# Interfaces.net
KiCad netlist of a schematic drawn in Altium Designer
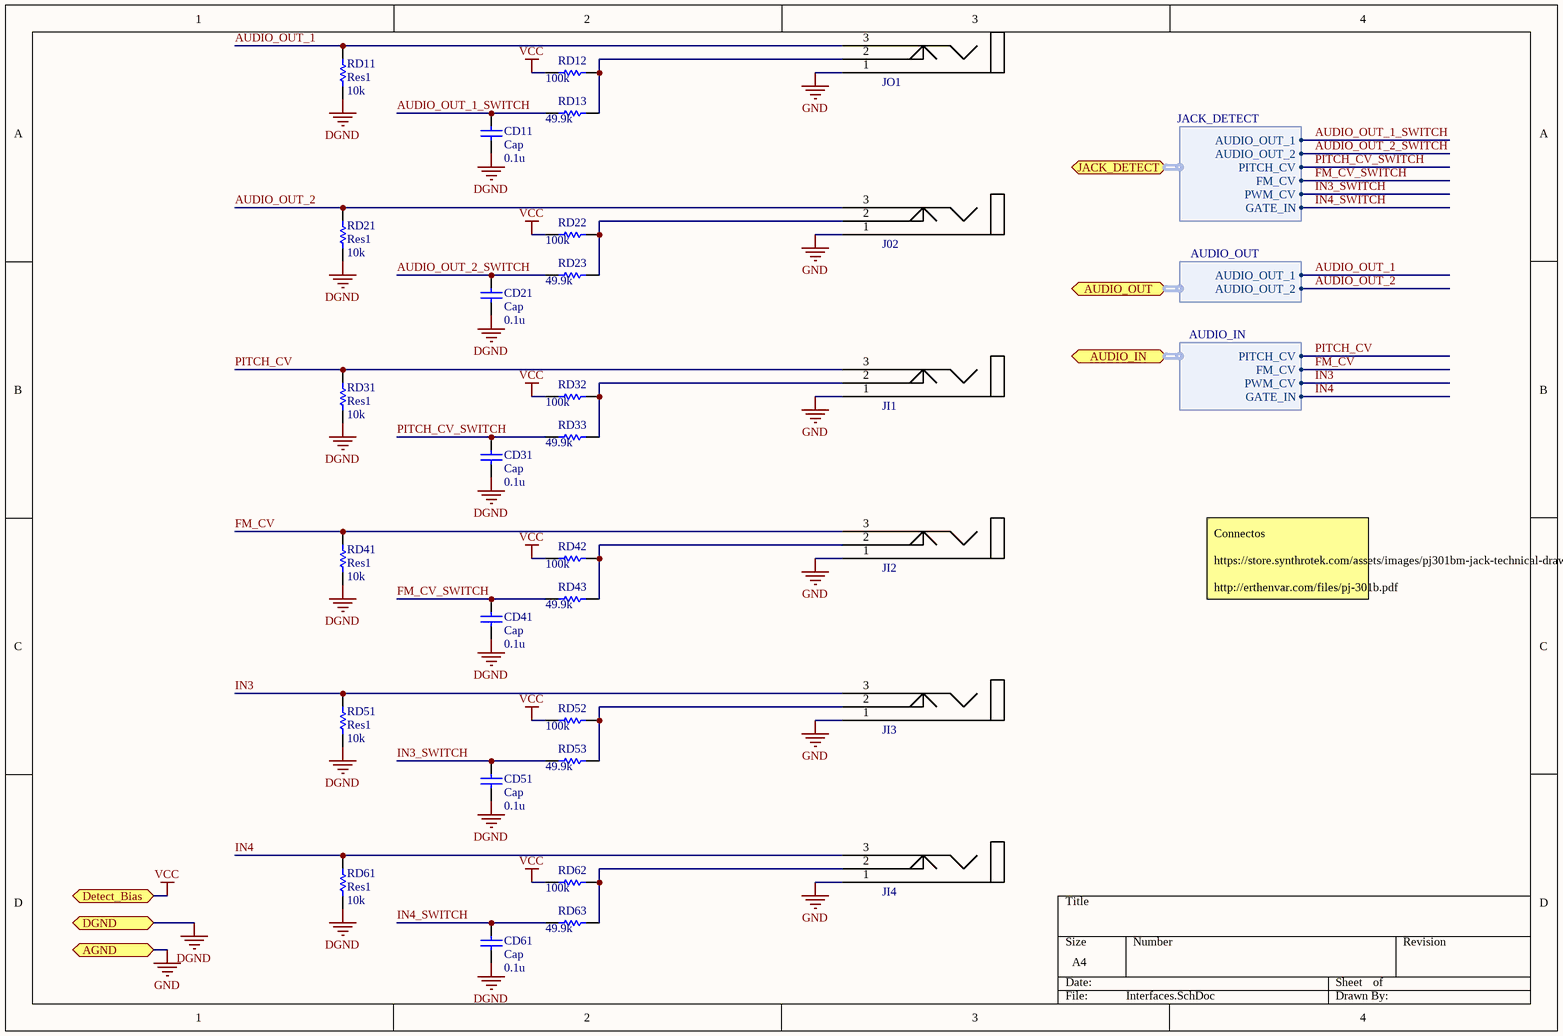
[diagram p0: Interfaces.SchDoc]

(export (version "E")
  (design (tool "Eeschema 10.0.6"))
  (components
    (comp (ref "CD11")
      (value "Cap")
      (footprint "C 0603 / 1608")
      (description "Capacitor")
      (fields (field (name "ALTIUM_VALUE") "0.1u") (field (name "PUBLISHER") "Altium Limited"))
      (libsource (lib "Standard") (part "Cap"))
    )
    (comp (ref "CD21")
      (value "Cap")
      (footprint "C 0603 / 1608")
      (description "Capacitor")
      (fields (field (name "ALTIUM_VALUE") "0.1u") (field (name "PUBLISHER") "Altium Limited"))
      (libsource (lib "Standard") (part "Cap"))
    )
    (comp (ref "CD31")
      (value "Cap")
      (footprint "C 0603 / 1608")
      (description "Capacitor")
      (fields (field (name "ALTIUM_VALUE") "0.1u") (field (name "PUBLISHER") "Altium Limited"))
      (libsource (lib "Standard") (part "Cap"))
    )
    (comp (ref "CD41")
      (value "Cap")
      (footprint "C 0603 / 1608")
      (description "Capacitor")
      (fields (field (name "ALTIUM_VALUE") "0.1u") (field (name "PUBLISHER") "Altium Limited"))
      (libsource (lib "Standard") (part "Cap"))
    )
    (comp (ref "CD51")
      (value "Cap")
      (footprint "C 0603 / 1608")
      (description "Capacitor")
      (fields (field (name "ALTIUM_VALUE") "0.1u") (field (name "PUBLISHER") "Altium Limited"))
      (libsource (lib "Standard") (part "Cap"))
    )
    (comp (ref "CD61")
      (value "Cap")
      (footprint "C 0603 / 1608")
      (description "Capacitor")
      (fields (field (name "ALTIUM_VALUE") "0.1u") (field (name "PUBLISHER") "Altium Limited"))
      (libsource (lib "Standard") (part "Cap"))
    )
    (comp (ref "J02") (value "PJ-301") (footprint "PJ-301BM") (libsource (lib "Connectors") (part "PJ-301")))
    (comp (ref "JI1") (value "PJ-301") (footprint "PJ-301BM") (libsource (lib "Connectors") (part "PJ-301")))
    (comp (ref "JI2") (value "PJ-301") (footprint "PJ-301BM") (libsource (lib "Connectors") (part "PJ-301")))
    (comp (ref "JI3") (value "PJ-301") (footprint "PJ-301BM") (libsource (lib "Connectors") (part "PJ-301")))
    (comp (ref "JI4") (value "PJ-301") (footprint "PJ-301BM") (libsource (lib "Connectors") (part "PJ-301")))
    (comp (ref "JO1") (value "PJ-301") (footprint "PJ-301BM") (libsource (lib "Connectors") (part "PJ-301")))
    (comp (ref "RD11")
      (value "Res1")
      (footprint "RES0603R")
      (description "Resistor")
      (fields (field (name "ALTIUM_VALUE") "10k") (field (name "PUBLISHER") "Altium Limited"))
      (libsource (lib "Standard") (part "Res1"))
    )
    (comp (ref "RD12")
      (value "100k")
      (footprint "RES0603R")
      (description "Resistor")
      (fields (field (name "Comment") "Res1") (field (name "PUBLISHER") "Altium Limited"))
      (libsource (lib "Standard") (part "Res1"))
    )
    (comp (ref "RD13")
      (value "49.9k")
      (footprint "RES0603R")
      (description "Resistor")
      (fields (field (name "Comment") "Res1") (field (name "PUBLISHER") "Altium Limited"))
      (libsource (lib "Standard") (part "Res1"))
    )
    (comp (ref "RD21")
      (value "Res1")
      (footprint "RES0603R")
      (description "Resistor")
      (fields (field (name "ALTIUM_VALUE") "10k") (field (name "PUBLISHER") "Altium Limited"))
      (libsource (lib "Standard") (part "Res1"))
    )
    (comp (ref "RD22")
      (value "100k")
      (footprint "RES0603R")
      (description "Resistor")
      (fields (field (name "Comment") "Res1") (field (name "PUBLISHER") "Altium Limited"))
      (libsource (lib "Standard") (part "Res1"))
    )
    (comp (ref "RD23")
      (value "49.9k")
      (footprint "RES0603R")
      (description "Resistor")
      (fields (field (name "Comment") "Res1") (field (name "PUBLISHER") "Altium Limited"))
      (libsource (lib "Standard") (part "Res1"))
    )
    (comp (ref "RD31")
      (value "Res1")
      (footprint "RES0603R")
      (description "Resistor")
      (fields (field (name "ALTIUM_VALUE") "10k") (field (name "PUBLISHER") "Altium Limited"))
      (libsource (lib "Standard") (part "Res1"))
    )
    (comp (ref "RD32")
      (value "100k")
      (footprint "RES0603R")
      (description "Resistor")
      (fields (field (name "Comment") "Res1") (field (name "PUBLISHER") "Altium Limited"))
      (libsource (lib "Standard") (part "Res1"))
    )
    (comp (ref "RD33")
      (value "49.9k")
      (footprint "RES0603R")
      (description "Resistor")
      (fields (field (name "Comment") "Res1") (field (name "PUBLISHER") "Altium Limited"))
      (libsource (lib "Standard") (part "Res1"))
    )
    (comp (ref "RD41")
      (value "Res1")
      (footprint "RES0603R")
      (description "Resistor")
      (fields (field (name "ALTIUM_VALUE") "10k") (field (name "PUBLISHER") "Altium Limited"))
      (libsource (lib "Standard") (part "Res1"))
    )
    (comp (ref "RD42")
      (value "100k")
      (footprint "RES0603R")
      (description "Resistor")
      (fields (field (name "Comment") "Res1") (field (name "PUBLISHER") "Altium Limited"))
      (libsource (lib "Standard") (part "Res1"))
    )
    (comp (ref "RD43")
      (value "49.9k")
      (footprint "RES0603R")
      (description "Resistor")
      (fields (field (name "Comment") "Res1") (field (name "PUBLISHER") "Altium Limited"))
      (libsource (lib "Standard") (part "Res1"))
    )
    (comp (ref "RD51")
      (value "Res1")
      (footprint "RES0603R")
      (description "Resistor")
      (fields (field (name "ALTIUM_VALUE") "10k") (field (name "PUBLISHER") "Altium Limited"))
      (libsource (lib "Standard") (part "Res1"))
    )
    (comp (ref "RD52")
      (value "100k")
      (footprint "RES0603R")
      (description "Resistor")
      (fields (field (name "Comment") "Res1") (field (name "PUBLISHER") "Altium Limited"))
      (libsource (lib "Standard") (part "Res1"))
    )
    (comp (ref "RD53")
      (value "49.9k")
      (footprint "RES0603R")
      (description "Resistor")
      (fields (field (name "Comment") "Res1") (field (name "PUBLISHER") "Altium Limited"))
      (libsource (lib "Standard") (part "Res1"))
    )
    (comp (ref "RD61")
      (value "Res1")
      (footprint "RES0603R")
      (description "Resistor")
      (fields (field (name "ALTIUM_VALUE") "10k") (field (name "PUBLISHER") "Altium Limited"))
      (libsource (lib "Standard") (part "Res1"))
    )
    (comp (ref "RD62")
      (value "100k")
      (footprint "RES0603R")
      (description "Resistor")
      (fields (field (name "Comment") "Res1") (field (name "PUBLISHER") "Altium Limited"))
      (libsource (lib "Standard") (part "Res1"))
    )
    (comp (ref "RD63")
      (value "49.9k")
      (footprint "RES0603R")
      (description "Resistor")
      (fields (field (name "Comment") "Res1") (field (name "PUBLISHER") "Altium Limited"))
      (libsource (lib "Standard") (part "Res1"))
    )
  )
  (nets
    (net (code "4") (name "/AUDIO_OUT_1") (class "Default")
      (node (ref "JO1") (pin "3") (pinfunction "Ring_3") (pintype "passive"))
      (node (ref "RD11") (pin "2") (pinfunction "2_2") (pintype "passive"))
    )
    (net (code "5") (name "/AUDIO_OUT_1_SWITCH") (class "Default")
      (node (ref "CD11") (pin "2") (pinfunction "2_2") (pintype "passive"))
      (node (ref "RD13") (pin "2") (pinfunction "2_2") (pintype "passive"))
    )
    (net (code "6") (name "/AUDIO_OUT_2") (class "Default")
      (node (ref "J02") (pin "3") (pinfunction "Ring_3") (pintype "passive"))
      (node (ref "RD21") (pin "2") (pinfunction "2_2") (pintype "passive"))
    )
    (net (code "7") (name "/AUDIO_OUT_2_SWITCH") (class "Default")
      (node (ref "CD21") (pin "2") (pinfunction "2_2") (pintype "passive"))
      (node (ref "RD23") (pin "2") (pinfunction "2_2") (pintype "passive"))
    )
    (net (code "8") (name "/FM_CV") (class "Default")
      (node (ref "JI2") (pin "3") (pinfunction "Ring_3") (pintype "passive"))
      (node (ref "RD41") (pin "2") (pinfunction "2_2") (pintype "passive"))
    )
    (net (code "9") (name "/FM_CV_SWITCH") (class "Default")
      (node (ref "CD41") (pin "2") (pinfunction "2_2") (pintype "passive"))
      (node (ref "RD43") (pin "2") (pinfunction "2_2") (pintype "passive"))
    )
    (net (code "10") (name "/IN3") (class "Default")
      (node (ref "JI3") (pin "3") (pinfunction "Ring_3") (pintype "passive"))
      (node (ref "RD51") (pin "2") (pinfunction "2_2") (pintype "passive"))
    )
    (net (code "11") (name "/IN3_SWITCH") (class "Default")
      (node (ref "CD51") (pin "2") (pinfunction "2_2") (pintype "passive"))
      (node (ref "RD53") (pin "2") (pinfunction "2_2") (pintype "passive"))
    )
    (net (code "12") (name "/IN4") (class "Default")
      (node (ref "JI4") (pin "3") (pinfunction "Ring_3") (pintype "passive"))
      (node (ref "RD61") (pin "2") (pinfunction "2_2") (pintype "passive"))
    )
    (net (code "13") (name "/IN4_SWITCH") (class "Default")
      (node (ref "CD61") (pin "2") (pinfunction "2_2") (pintype "passive"))
      (node (ref "RD63") (pin "2") (pinfunction "2_2") (pintype "passive"))
    )
    (net (code "14") (name "/PITCH_CV") (class "Default")
      (node (ref "JI1") (pin "3") (pinfunction "Ring_3") (pintype "passive"))
      (node (ref "RD31") (pin "2") (pinfunction "2_2") (pintype "passive"))
    )
    (net (code "15") (name "/PITCH_CV_SWITCH") (class "Default")
      (node (ref "CD31") (pin "2") (pinfunction "2_2") (pintype "passive"))
      (node (ref "RD33") (pin "2") (pinfunction "2_2") (pintype "passive"))
    )
    (net (code "19") (name "DGND") (class "Default")
      (node (ref "CD11") (pin "1") (pinfunction "1_1") (pintype "passive"))
      (node (ref "CD21") (pin "1") (pinfunction "1_1") (pintype "passive"))
      (node (ref "CD31") (pin "1") (pinfunction "1_1") (pintype "passive"))
      (node (ref "CD41") (pin "1") (pinfunction "1_1") (pintype "passive"))
      (node (ref "CD51") (pin "1") (pinfunction "1_1") (pintype "passive"))
      (node (ref "CD61") (pin "1") (pinfunction "1_1") (pintype "passive"))
      (node (ref "RD11") (pin "1") (pinfunction "1_1") (pintype "passive"))
      (node (ref "RD21") (pin "1") (pinfunction "1_1") (pintype "passive"))
      (node (ref "RD31") (pin "1") (pinfunction "1_1") (pintype "passive"))
      (node (ref "RD41") (pin "1") (pinfunction "1_1") (pintype "passive"))
      (node (ref "RD51") (pin "1") (pinfunction "1_1") (pintype "passive"))
      (node (ref "RD61") (pin "1") (pinfunction "1_1") (pintype "passive"))
    )
    (net (code "20") (name "GND") (class "Default")
      (node (ref "J02") (pin "1") (pinfunction "Sleeve_1") (pintype "passive"))
      (node (ref "JI1") (pin "1") (pinfunction "Sleeve_1") (pintype "passive"))
      (node (ref "JI2") (pin "1") (pinfunction "Sleeve_1") (pintype "passive"))
      (node (ref "JI3") (pin "1") (pinfunction "Sleeve_1") (pintype "passive"))
      (node (ref "JI4") (pin "1") (pinfunction "Sleeve_1") (pintype "passive"))
      (node (ref "JO1") (pin "1") (pinfunction "Sleeve_1") (pintype "passive"))
    )
    (net (code "21") (name "Net-(J02-Tip)") (class "Default")
      (node (ref "J02") (pin "2") (pinfunction "Tip_2") (pintype "passive"))
      (node (ref "RD22") (pin "1") (pinfunction "1_1") (pintype "passive"))
      (node (ref "RD23") (pin "1") (pinfunction "1_1") (pintype "passive"))
    )
    (net (code "22") (name "Net-(JI1-Tip)") (class "Default")
      (node (ref "JI1") (pin "2") (pinfunction "Tip_2") (pintype "passive"))
      (node (ref "RD32") (pin "1") (pinfunction "1_1") (pintype "passive"))
      (node (ref "RD33") (pin "1") (pinfunction "1_1") (pintype "passive"))
    )
    (net (code "23") (name "Net-(JI2-Tip)") (class "Default")
      (node (ref "JI2") (pin "2") (pinfunction "Tip_2") (pintype "passive"))
      (node (ref "RD42") (pin "1") (pinfunction "1_1") (pintype "passive"))
      (node (ref "RD43") (pin "1") (pinfunction "1_1") (pintype "passive"))
    )
    (net (code "24") (name "Net-(JI3-Tip)") (class "Default")
      (node (ref "JI3") (pin "2") (pinfunction "Tip_2") (pintype "passive"))
      (node (ref "RD52") (pin "1") (pinfunction "1_1") (pintype "passive"))
      (node (ref "RD53") (pin "1") (pinfunction "1_1") (pintype "passive"))
    )
    (net (code "25") (name "Net-(JI4-Tip)") (class "Default")
      (node (ref "JI4") (pin "2") (pinfunction "Tip_2") (pintype "passive"))
      (node (ref "RD62") (pin "1") (pinfunction "1_1") (pintype "passive"))
      (node (ref "RD63") (pin "1") (pinfunction "1_1") (pintype "passive"))
    )
    (net (code "26") (name "Net-(JO1-Tip)") (class "Default")
      (node (ref "JO1") (pin "2") (pinfunction "Tip_2") (pintype "passive"))
      (node (ref "RD12") (pin "1") (pinfunction "1_1") (pintype "passive"))
      (node (ref "RD13") (pin "1") (pinfunction "1_1") (pintype "passive"))
    )
    (net (code "27") (name "VCC") (class "Default")
      (node (ref "RD12") (pin "2") (pinfunction "2_2") (pintype "passive"))
      (node (ref "RD22") (pin "2") (pinfunction "2_2") (pintype "passive"))
      (node (ref "RD32") (pin "2") (pinfunction "2_2") (pintype "passive"))
      (node (ref "RD42") (pin "2") (pinfunction "2_2") (pintype "passive"))
      (node (ref "RD52") (pin "2") (pinfunction "2_2") (pintype "passive"))
      (node (ref "RD62") (pin "2") (pinfunction "2_2") (pintype "passive"))
    )
  )
)
